# PolluxWakeupShield.net
KiCad netlist of a schematic drawn in EAGLE
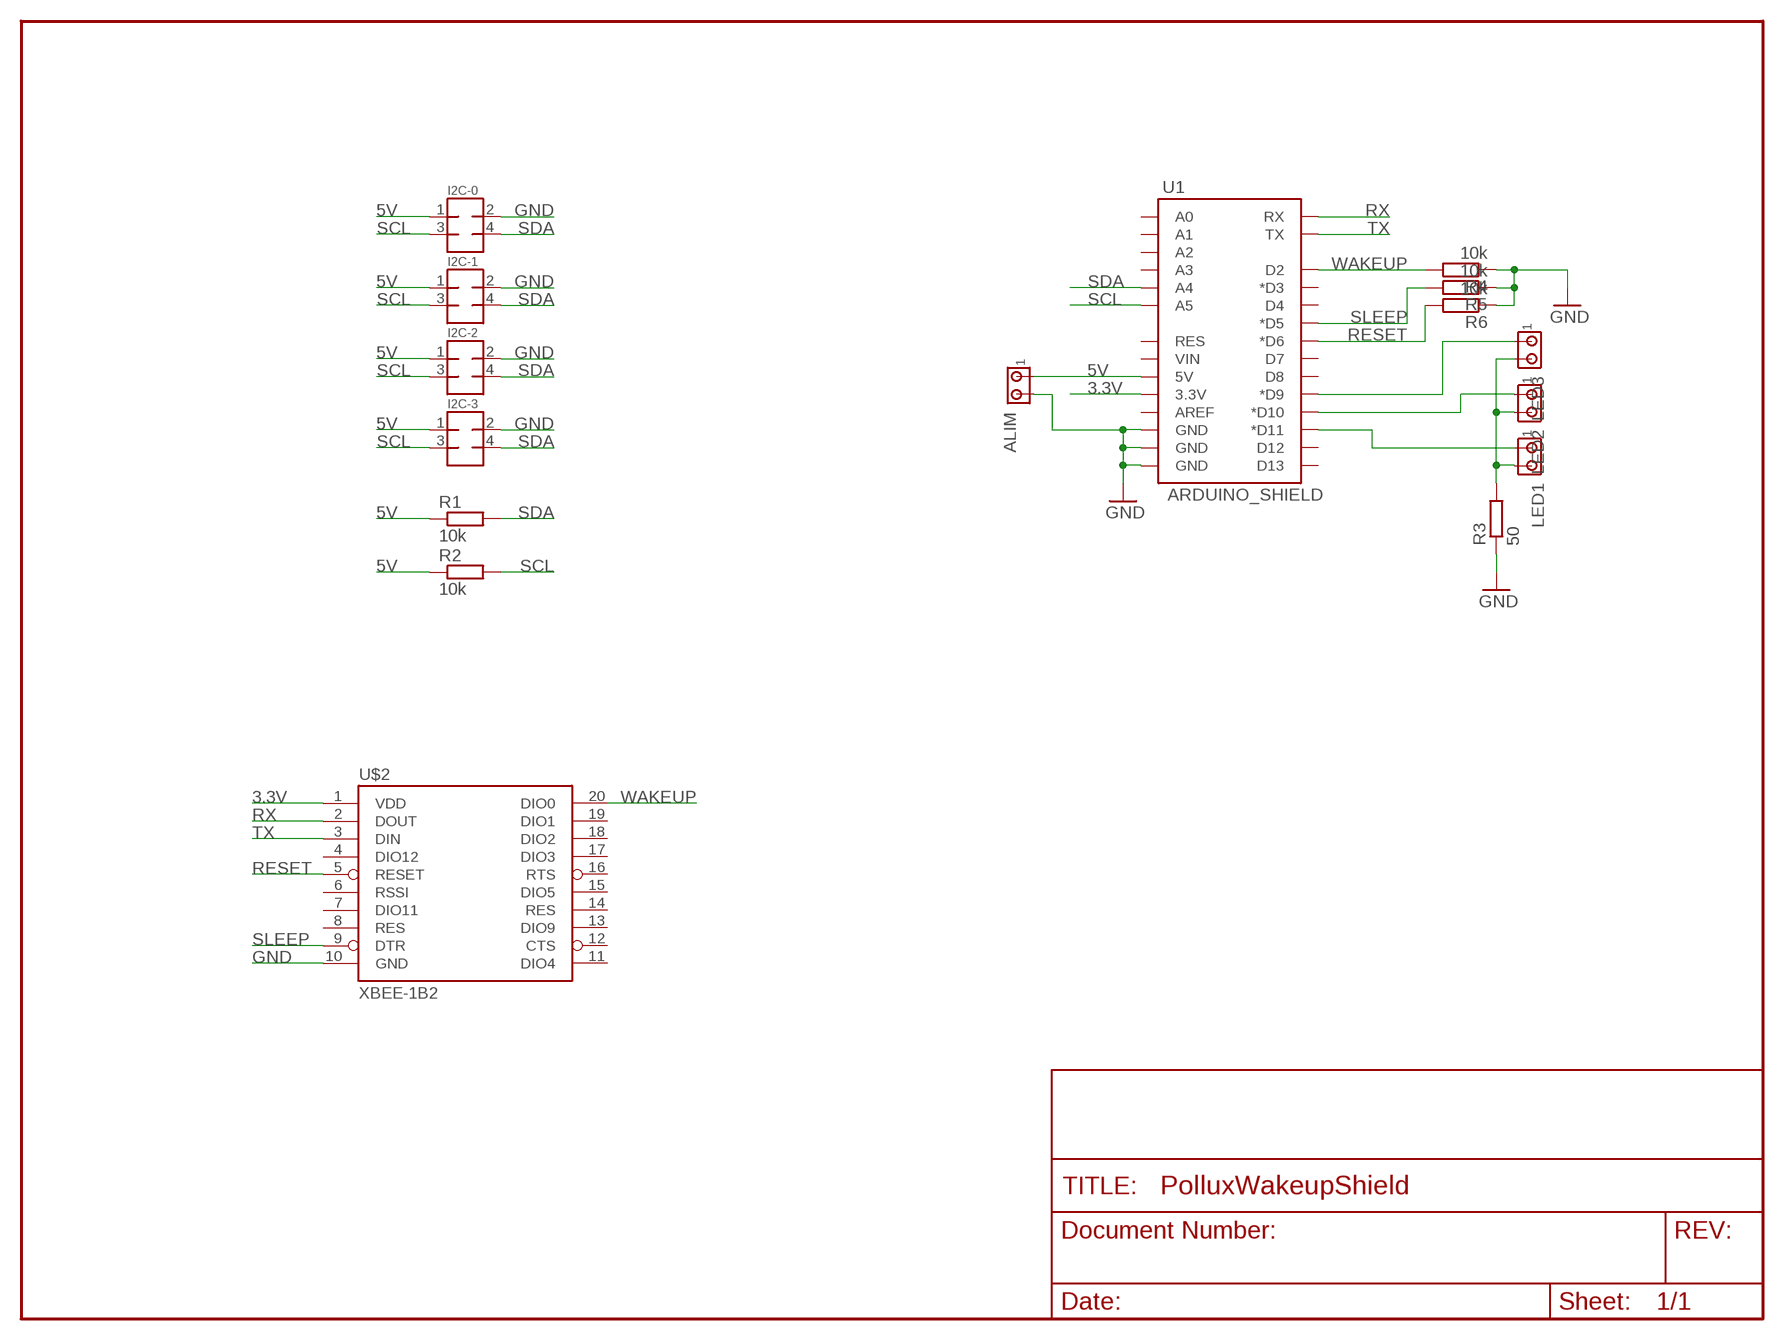
[diagram p0: schematic, sheet 1]

(export (version "E")
  (design (tool "Eeschema 10.0.6"))
  (components
    (comp (ref "ALIM")
      (value "MTA02-100")
      (footprint "eagle-import:10X02MTA")
      (libsource (lib "eagle-import") (part "MTA02-100"))
    )
    (comp (ref "I2C-0")
      (value "MMATCH-4-PTH")
      (footprint "eagle-import:AMP-215079-4")
      (libsource (lib "eagle-import") (part "MMATCH-4-PTH"))
    )
    (comp (ref "I2C-1")
      (value "MMATCH-4-PTH")
      (footprint "eagle-import:AMP-215079-4")
      (libsource (lib "eagle-import") (part "MMATCH-4-PTH"))
    )
    (comp (ref "I2C-2")
      (value "MMATCH-4-PTH")
      (footprint "eagle-import:AMP-215079-4")
      (libsource (lib "eagle-import") (part "MMATCH-4-PTH"))
    )
    (comp (ref "I2C-3")
      (value "MMATCH-4-PTH")
      (footprint "eagle-import:AMP-215079-4")
      (libsource (lib "eagle-import") (part "MMATCH-4-PTH"))
    )
    (comp (ref "LED1")
      (value "MTA02-100")
      (footprint "eagle-import:10X02MTA")
      (libsource (lib "eagle-import") (part "MTA02-100"))
    )
    (comp (ref "LED2")
      (value "MTA02-100")
      (footprint "eagle-import:10X02MTA")
      (libsource (lib "eagle-import") (part "MTA02-100"))
    )
    (comp (ref "LED3")
      (value "MTA02-100")
      (footprint "eagle-import:10X02MTA")
      (libsource (lib "eagle-import") (part "MTA02-100"))
    )
    (comp (ref "R1")
      (value "10k")
      (footprint "eagle-import:0204_7")
      (libsource (lib "eagle-import") (part "R-EU_0204/7"))
    )
    (comp (ref "R2")
      (value "10k")
      (footprint "eagle-import:0204_7")
      (libsource (lib "eagle-import") (part "R-EU_0204/7"))
    )
    (comp (ref "R3")
      (value "50")
      (footprint "eagle-import:0204_7")
      (libsource (lib "eagle-import") (part "R-EU_0204/7"))
    )
    (comp (ref "R4")
      (value "10k")
      (footprint "eagle-import:0204_7")
      (libsource (lib "eagle-import") (part "R-EU_0204/7"))
    )
    (comp (ref "R5")
      (value "10k")
      (footprint "eagle-import:0204_7")
      (libsource (lib "eagle-import") (part "R-EU_0204/7"))
    )
    (comp (ref "R6")
      (value "10k")
      (footprint "eagle-import:0204_7")
      (libsource (lib "eagle-import") (part "R-EU_0204/7"))
    )
    (comp (ref "U$2")
      (value "XBEE-1B2")
      (footprint "eagle-import:XBEE-SILK")
      (libsource (lib "eagle-import") (part "XBEE-1B2"))
    )
    (comp (ref "U1")
      (value "ARDUINO_SHIELD")
      (footprint "eagle-import:DUEMILANOVE_SHIELD")
      (libsource (lib "eagle-import") (part "ARDUINO_SHIELDLABEL"))
    )
  )
  (nets
    (net (code "1") (name "/3.3V") (class "Default")
      (node (ref "U$2") (pin "1") (pinfunction "VDD_1") (pintype "power_in"))
      (node (ref "U1") (pin "3.3V") (pinfunction "3.3V_3.3V") (pintype "bidirectional"))
    )
    (net (code "2") (name "/5V") (class "Default")
      (node (ref "ALIM") (pin "1") (pinfunction "1_1") (pintype "passive"))
      (node (ref "I2C-0") (pin "1") (pinfunction "1_1") (pintype "bidirectional"))
      (node (ref "I2C-1") (pin "1") (pinfunction "1_1") (pintype "bidirectional"))
      (node (ref "I2C-2") (pin "1") (pinfunction "1_1") (pintype "bidirectional"))
      (node (ref "I2C-3") (pin "1") (pinfunction "1_1") (pintype "bidirectional"))
      (node (ref "R1") (pin "1") (pinfunction "1_1") (pintype "passive"))
      (node (ref "R2") (pin "1") (pinfunction "1_1") (pintype "passive"))
      (node (ref "U1") (pin "5V") (pinfunction "5V_5V") (pintype "bidirectional"))
    )
    (net (code "3") (name "/RESET") (class "Default")
      (node (ref "R6") (pin "2") (pinfunction "2_2") (pintype "passive"))
      (node (ref "U$2") (pin "5") (pinfunction "RESET_5") (pintype "input"))
      (node (ref "U1") (pin "D6") (pinfunction "*D6_D6") (pintype "bidirectional"))
    )
    (net (code "4") (name "/RX") (class "Default")
      (node (ref "U$2") (pin "2") (pinfunction "DOUT_2") (pintype "output"))
      (node (ref "U1") (pin "RX") (pinfunction "RX_RX") (pintype "bidirectional"))
    )
    (net (code "5") (name "/SCL") (class "Default")
      (node (ref "I2C-0") (pin "3") (pinfunction "3_3") (pintype "bidirectional"))
      (node (ref "I2C-1") (pin "3") (pinfunction "3_3") (pintype "bidirectional"))
      (node (ref "I2C-2") (pin "3") (pinfunction "3_3") (pintype "bidirectional"))
      (node (ref "I2C-3") (pin "3") (pinfunction "3_3") (pintype "bidirectional"))
      (node (ref "R2") (pin "2") (pinfunction "2_2") (pintype "passive"))
      (node (ref "U1") (pin "A5") (pinfunction "A5_A5") (pintype "bidirectional"))
    )
    (net (code "6") (name "/SDA") (class "Default")
      (node (ref "I2C-0") (pin "4") (pinfunction "4_4") (pintype "bidirectional"))
      (node (ref "I2C-1") (pin "4") (pinfunction "4_4") (pintype "bidirectional"))
      (node (ref "I2C-2") (pin "4") (pinfunction "4_4") (pintype "bidirectional"))
      (node (ref "I2C-3") (pin "4") (pinfunction "4_4") (pintype "bidirectional"))
      (node (ref "R1") (pin "2") (pinfunction "2_2") (pintype "passive"))
      (node (ref "U1") (pin "A4") (pinfunction "A4_A4") (pintype "bidirectional"))
    )
    (net (code "7") (name "/SLEEP") (class "Default")
      (node (ref "R5") (pin "2") (pinfunction "2_2") (pintype "passive"))
      (node (ref "U$2") (pin "9") (pinfunction "DTR_9") (pintype "bidirectional"))
      (node (ref "U1") (pin "D5") (pinfunction "*D5_D5") (pintype "bidirectional"))
    )
    (net (code "8") (name "/TX") (class "Default")
      (node (ref "U$2") (pin "3") (pinfunction "DIN_3") (pintype "input"))
      (node (ref "U1") (pin "TX") (pinfunction "TX_TX") (pintype "bidirectional"))
    )
    (net (code "9") (name "/WAKEUP") (class "Default")
      (node (ref "R4") (pin "2") (pinfunction "2_2") (pintype "passive"))
      (node (ref "U$2") (pin "20") (pinfunction "DIO0_20") (pintype "bidirectional"))
      (node (ref "U1") (pin "D2") (pinfunction "D2_D2") (pintype "bidirectional"))
    )
    (net (code "10") (name "GND") (class "Default")
      (node (ref "ALIM") (pin "2") (pinfunction "2_2") (pintype "passive"))
      (node (ref "I2C-0") (pin "2") (pinfunction "2_2") (pintype "bidirectional"))
      (node (ref "I2C-1") (pin "2") (pinfunction "2_2") (pintype "bidirectional"))
      (node (ref "I2C-2") (pin "2") (pinfunction "2_2") (pintype "bidirectional"))
      (node (ref "I2C-3") (pin "2") (pinfunction "2_2") (pintype "bidirectional"))
      (node (ref "R3") (pin "1") (pinfunction "1_1") (pintype "passive"))
      (node (ref "R4") (pin "1") (pinfunction "1_1") (pintype "passive"))
      (node (ref "R5") (pin "1") (pinfunction "1_1") (pintype "passive"))
      (node (ref "R6") (pin "1") (pinfunction "1_1") (pintype "passive"))
      (node (ref "U$2") (pin "10") (pinfunction "GND_10") (pintype "power_in"))
      (node (ref "U1") (pin "GND@0") (pinfunction "GND_GND@0") (pintype "bidirectional"))
      (node (ref "U1") (pin "GND@1") (pinfunction "GND_GND@1") (pintype "bidirectional"))
      (node (ref "U1") (pin "GND@2") (pinfunction "GND_GND@2") (pintype "bidirectional"))
    )
    (net (code "11") (name "Net-(LED1-Pad2)") (class "Default")
      (node (ref "LED1") (pin "2") (pinfunction "2_2") (pintype "passive"))
      (node (ref "LED2") (pin "2") (pinfunction "2_2") (pintype "passive"))
      (node (ref "LED3") (pin "2") (pinfunction "2_2") (pintype "passive"))
      (node (ref "R3") (pin "2") (pinfunction "2_2") (pintype "passive"))
    )
    (net (code "12") (name "Net-(U1-*D9)") (class "Default")
      (node (ref "LED3") (pin "1") (pinfunction "1_1") (pintype "passive"))
      (node (ref "U1") (pin "D9") (pinfunction "*D9_D9") (pintype "bidirectional"))
    )
    (net (code "13") (name "Net-(U1-*D10)") (class "Default")
      (node (ref "LED2") (pin "1") (pinfunction "1_1") (pintype "passive"))
      (node (ref "U1") (pin "D10") (pinfunction "*D10_D10") (pintype "bidirectional"))
    )
    (net (code "14") (name "Net-(U1-*D11)") (class "Default")
      (node (ref "LED1") (pin "1") (pinfunction "1_1") (pintype "passive"))
      (node (ref "U1") (pin "D11") (pinfunction "*D11_D11") (pintype "bidirectional"))
    )
    (net (code "15") (name "unconnected-(U$2-CTS-Pad12)") (class "Default")
      (node (ref "U$2") (pin "12") (pinfunction "CTS_12") (pintype "output"))
    )
    (net (code "16") (name "unconnected-(U$2-DIO1-Pad19)") (class "Default")
      (node (ref "U$2") (pin "19") (pinfunction "DIO1_19") (pintype "bidirectional"))
    )
    (net (code "17") (name "unconnected-(U$2-DIO2-Pad18)") (class "Default")
      (node (ref "U$2") (pin "18") (pinfunction "DIO2_18") (pintype "bidirectional"))
    )
    (net (code "18") (name "unconnected-(U$2-DIO3-Pad17)") (class "Default")
      (node (ref "U$2") (pin "17") (pinfunction "DIO3_17") (pintype "bidirectional"))
    )
    (net (code "19") (name "unconnected-(U$2-DIO4-Pad11)") (class "Default")
      (node (ref "U$2") (pin "11") (pinfunction "DIO4_11") (pintype "bidirectional"))
    )
    (net (code "20") (name "unconnected-(U$2-DIO5-Pad15)") (class "Default")
      (node (ref "U$2") (pin "15") (pinfunction "DIO5_15") (pintype "bidirectional"))
    )
    (net (code "21") (name "unconnected-(U$2-DIO9-Pad13)") (class "Default")
      (node (ref "U$2") (pin "13") (pinfunction "DIO9_13") (pintype "bidirectional"))
    )
    (net (code "22") (name "unconnected-(U$2-DIO11-Pad7)") (class "Default")
      (node (ref "U$2") (pin "7") (pinfunction "DIO11_7") (pintype "bidirectional"))
    )
    (net (code "23") (name "unconnected-(U$2-DIO12-Pad4)") (class "Default")
      (node (ref "U$2") (pin "4") (pinfunction "DIO12_4") (pintype "bidirectional"))
    )
    (net (code "24") (name "unconnected-(U$2-RES-Pad8)") (class "Default")
      (node (ref "U$2") (pin "8") (pinfunction "RES_8") (pintype "bidirectional"))
    )
    (net (code "25") (name "unconnected-(U$2-RES-Pad14)") (class "Default")
      (node (ref "U$2") (pin "14") (pinfunction "RES_14") (pintype "bidirectional"))
    )
    (net (code "26") (name "unconnected-(U$2-RSSI-Pad6)") (class "Default")
      (node (ref "U$2") (pin "6") (pinfunction "RSSI_6") (pintype "bidirectional"))
    )
    (net (code "27") (name "unconnected-(U$2-RTS-Pad16)") (class "Default")
      (node (ref "U$2") (pin "16") (pinfunction "RTS_16") (pintype "input"))
    )
    (net (code "28") (name "unconnected-(U1-*D3-PadD3)") (class "Default")
      (node (ref "U1") (pin "D3") (pinfunction "*D3_D3") (pintype "bidirectional"))
    )
    (net (code "29") (name "unconnected-(U1-PadA0)") (class "Default")
      (node (ref "U1") (pin "A0") (pinfunction "A0_A0") (pintype "bidirectional"))
    )
    (net (code "30") (name "unconnected-(U1-PadA1)") (class "Default")
      (node (ref "U1") (pin "A1") (pinfunction "A1_A1") (pintype "bidirectional"))
    )
    (net (code "31") (name "unconnected-(U1-PadA2)") (class "Default")
      (node (ref "U1") (pin "A2") (pinfunction "A2_A2") (pintype "bidirectional"))
    )
    (net (code "32") (name "unconnected-(U1-PadA3)") (class "Default")
      (node (ref "U1") (pin "A3") (pinfunction "A3_A3") (pintype "bidirectional"))
    )
    (net (code "33") (name "unconnected-(U1-PadAREF)") (class "Default")
      (node (ref "U1") (pin "AREF") (pinfunction "AREF_AREF") (pintype "bidirectional"))
    )
    (net (code "34") (name "unconnected-(U1-PadD4)") (class "Default")
      (node (ref "U1") (pin "D4") (pinfunction "D4_D4") (pintype "bidirectional"))
    )
    (net (code "35") (name "unconnected-(U1-PadD7)") (class "Default")
      (node (ref "U1") (pin "D7") (pinfunction "D7_D7") (pintype "bidirectional"))
    )
    (net (code "36") (name "unconnected-(U1-PadD8)") (class "Default")
      (node (ref "U1") (pin "D8") (pinfunction "D8_D8") (pintype "bidirectional"))
    )
    (net (code "37") (name "unconnected-(U1-PadD12)") (class "Default")
      (node (ref "U1") (pin "D12") (pinfunction "D12_D12") (pintype "bidirectional"))
    )
    (net (code "38") (name "unconnected-(U1-PadD13)") (class "Default")
      (node (ref "U1") (pin "D13") (pinfunction "D13_D13") (pintype "bidirectional"))
    )
    (net (code "39") (name "unconnected-(U1-PadRES)") (class "Default")
      (node (ref "U1") (pin "RES") (pinfunction "RES_RES") (pintype "bidirectional"))
    )
    (net (code "40") (name "unconnected-(U1-PadVIN)") (class "Default")
      (node (ref "U1") (pin "VIN") (pinfunction "VIN_VIN") (pintype "bidirectional"))
    )
  )
)
